# Xilinx_DDR.net
KiCad netlist of a schematic drawn in Altium Designer
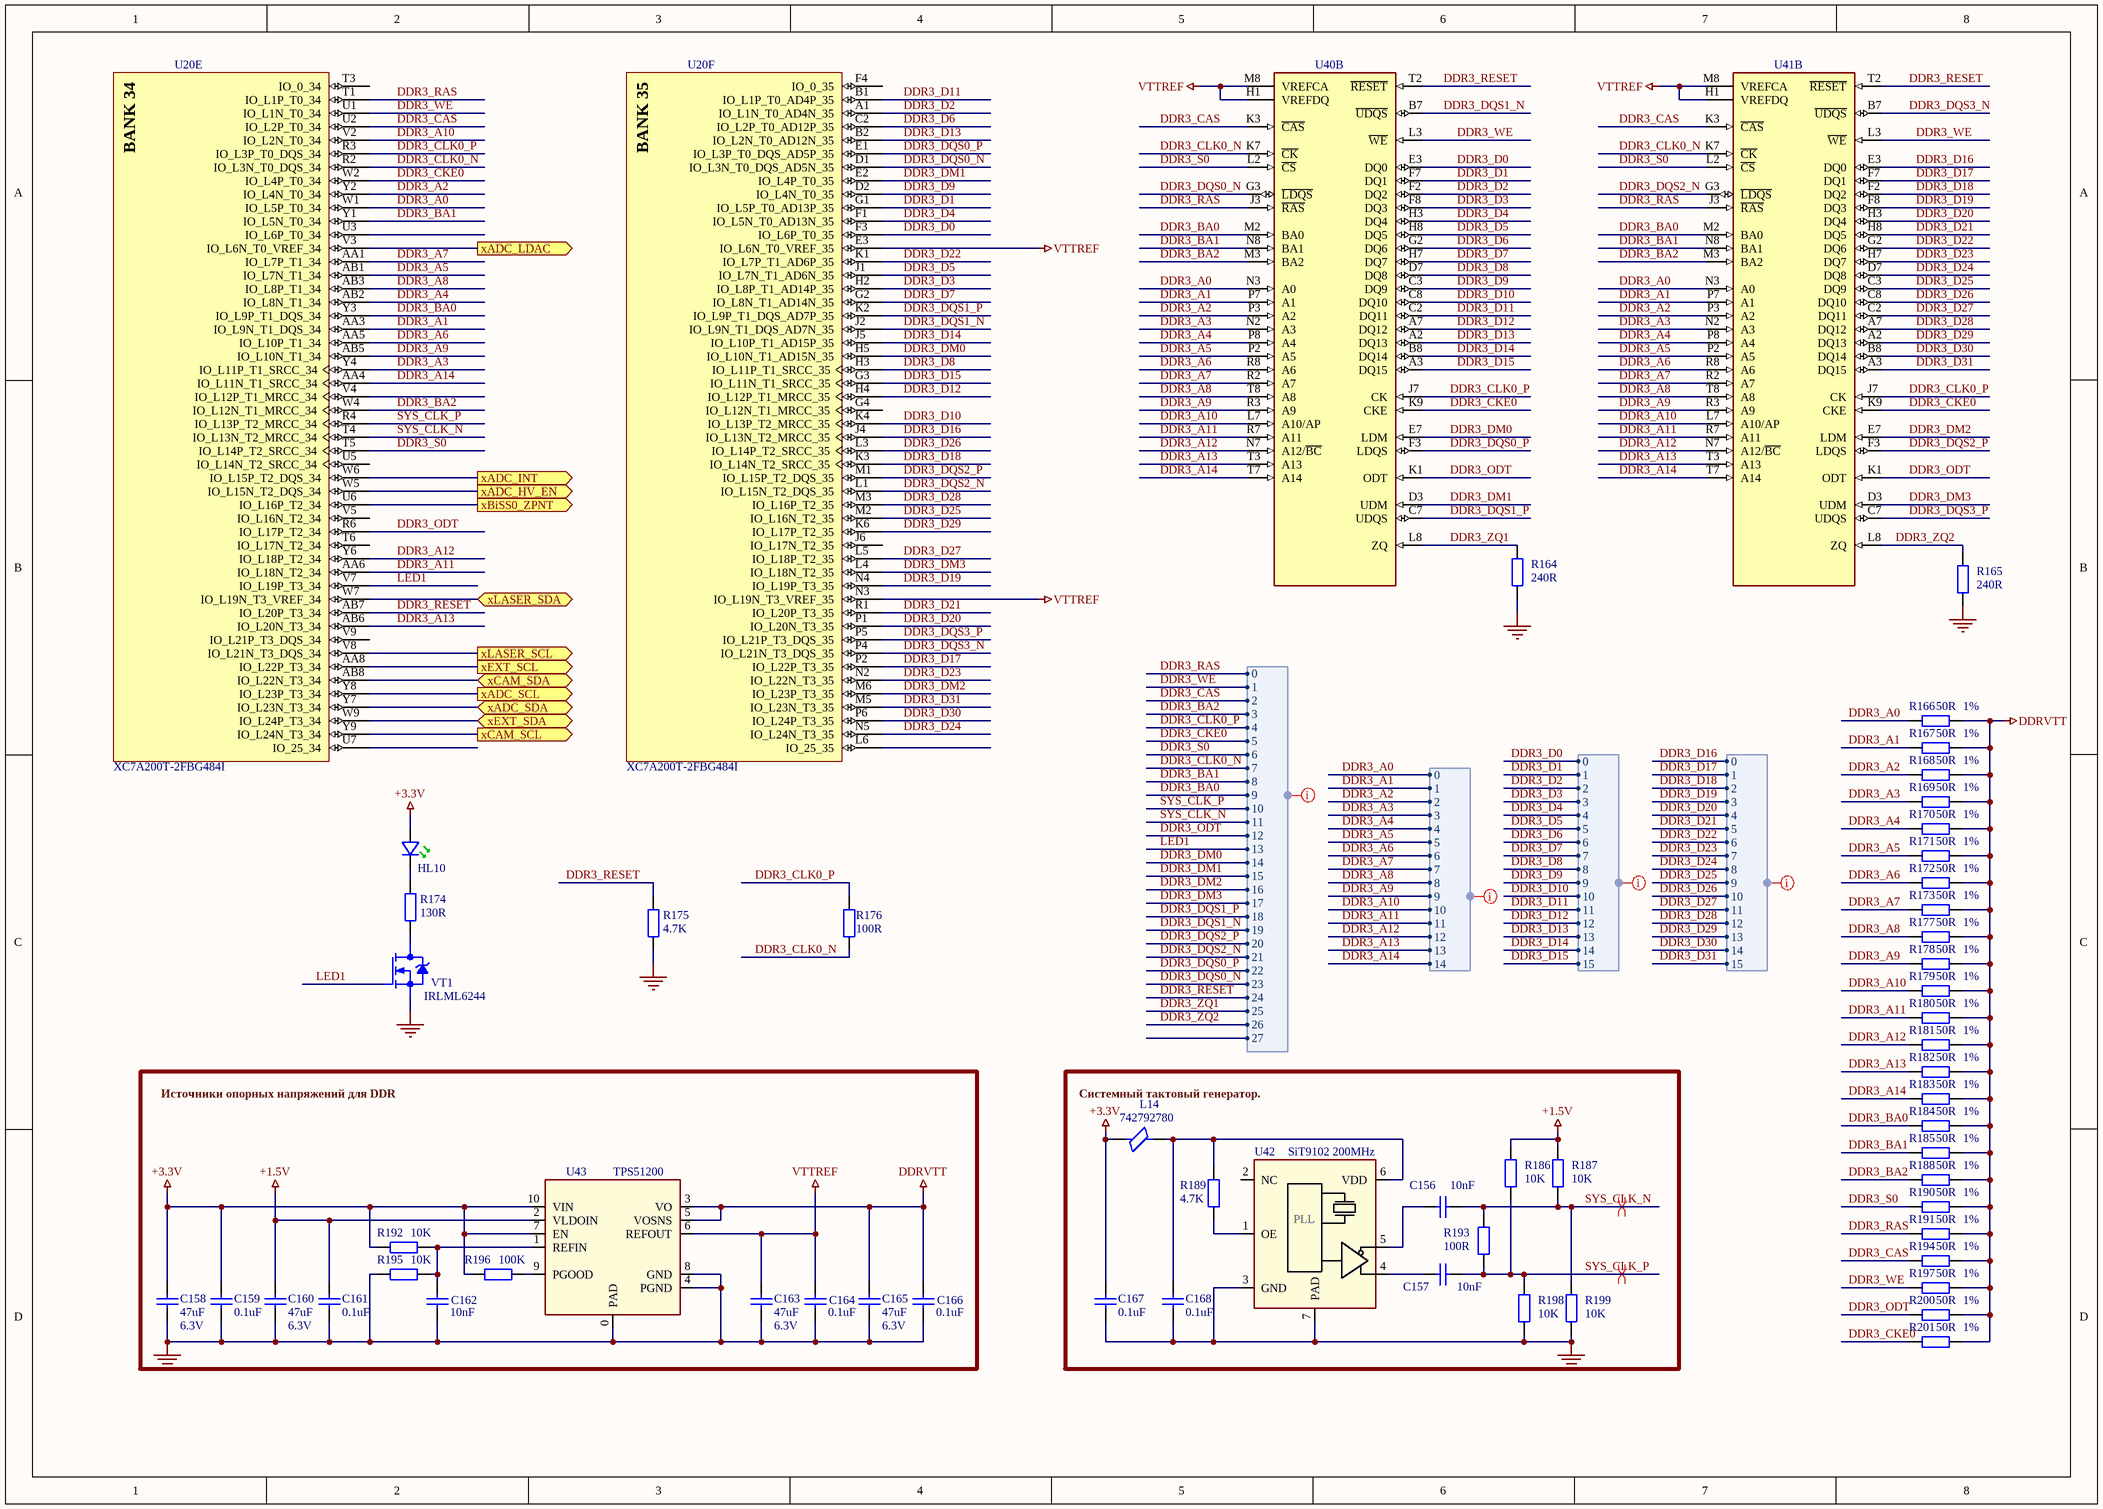
[diagram p0: Xilinx_DDR.SchDoc]

(export (version "E")
  (design (tool "Eeschema 10.0.6"))
  (components
    (comp (ref "C156")
      (value "10nF")
      (footprint "C0402")
      (description "Конденсатор керамический")
      (fields (field (name "VOLTAGE") "25V") (field (name "Comment") "Cap"))
      (libsource (lib "Terra") (part "Cap"))
    )
    (comp (ref "C157")
      (value "10nF")
      (footprint "C0402")
      (description "Конденсатор керамический")
      (fields (field (name "VOLTAGE") "25V") (field (name "Comment") "Cap"))
      (libsource (lib "Terra") (part "Cap"))
    )
    (comp (ref "C158")
      (value "47uF")
      (footprint "C0805")
      (description "C0805C476M9PAC")
      (fields (field (name "VOLTAGE") "6.3V") (field (name "Comment") "Cap"))
      (libsource (lib "Terra") (part "Cap"))
    )
    (comp (ref "C159")
      (value "0.1uF")
      (footprint "C0402")
      (description "Конденсатор керамический")
      (fields (field (name "VOLTAGE") "25V") (field (name "Comment") "Cap"))
      (libsource (lib "Terra") (part "Cap"))
    )
    (comp (ref "C160")
      (value "47uF")
      (footprint "C0805")
      (description "C0805C476M9PAC")
      (fields (field (name "VOLTAGE") "6.3V") (field (name "Comment") "Cap"))
      (libsource (lib "Terra") (part "Cap"))
    )
    (comp (ref "C161")
      (value "0.1uF")
      (footprint "C0402")
      (description "Конденсатор керамический")
      (fields (field (name "VOLTAGE") "25V") (field (name "Comment") "Cap"))
      (libsource (lib "Terra") (part "Cap"))
    )
    (comp (ref "C162")
      (value "10nF")
      (footprint "C0402")
      (description "Конденсатор керамический")
      (fields (field (name "VOLTAGE") "25V") (field (name "Comment") "Cap"))
      (libsource (lib "Terra") (part "Cap"))
    )
    (comp (ref "C163")
      (value "47uF")
      (footprint "C0805")
      (description "C0805C476M9PAC")
      (fields (field (name "VOLTAGE") "6.3V") (field (name "Comment") "Cap"))
      (libsource (lib "Terra") (part "Cap"))
    )
    (comp (ref "C164")
      (value "0.1uF")
      (footprint "C0402")
      (description "Конденсатор керамический")
      (fields (field (name "VOLTAGE") "25V") (field (name "Comment") "Cap"))
      (libsource (lib "Terra") (part "Cap"))
    )
    (comp (ref "C165")
      (value "47uF")
      (footprint "C0805")
      (description "C0805C476M9PAC")
      (fields (field (name "VOLTAGE") "6.3V") (field (name "Comment") "Cap"))
      (libsource (lib "Terra") (part "Cap"))
    )
    (comp (ref "C166")
      (value "0.1uF")
      (footprint "C0402")
      (description "Конденсатор керамический")
      (fields (field (name "VOLTAGE") "25V") (field (name "Comment") "Cap"))
      (libsource (lib "Terra") (part "Cap"))
    )
    (comp (ref "C167")
      (value "0.1uF")
      (footprint "C0402")
      (description "Конденсатор керамический")
      (fields (field (name "VOLTAGE") "25V") (field (name "Comment") "Cap"))
      (libsource (lib "Terra") (part "Cap"))
    )
    (comp (ref "C168")
      (value "0.1uF")
      (footprint "C0402")
      (description "Конденсатор керамический")
      (fields (field (name "VOLTAGE") "25V") (field (name "Comment") "Cap"))
      (libsource (lib "Terra") (part "Cap"))
    )
    (comp (ref "HL10")
      (value "~")
      (footprint "KP-1608_16x08x11_L")
      (description "1.6X0.8mm SMD  LED")
      (libsource (lib "Terra") (part "ledG_KP-1608MGC_KP-1608"))
    )
    (comp (ref "L14")
      (value "742792780")
      (footprint "L0402")
      (description "Wurth Elektronik EMI FILTERS FERRITE BEAD, 220R@100MHz, 0.35R")
      (libsource (lib "Terra") (part "BEAD_FERRITE_SM"))
    )
    (comp (ref "R164")
      (value "240R")
      (footprint "R0402")
      (description "Резистор")
      (fields (field (name "Comment") "Res2"))
      (libsource (lib "") (part "Res2_2"))
    )
    (comp (ref "R165")
      (value "240R")
      (footprint "R0402")
      (description "Резистор")
      (fields (field (name "Comment") "Res2"))
      (libsource (lib "") (part "Res2_2"))
    )
    (comp (ref "R166")
      (value "50R")
      (footprint "R0402")
      (description "Резистор")
      (fields (field (name "PRECISION") "1%") (field (name "Comment") "Res2"))
      (libsource (lib "Terra") (part "Res2"))
    )
    (comp (ref "R167")
      (value "50R")
      (footprint "R0402")
      (description "Резистор")
      (fields (field (name "PRECISION") "1%") (field (name "Comment") "Res2"))
      (libsource (lib "Terra") (part "Res2"))
    )
    (comp (ref "R168")
      (value "50R")
      (footprint "R0402")
      (description "Резистор")
      (fields (field (name "PRECISION") "1%") (field (name "Comment") "Res2"))
      (libsource (lib "Terra") (part "Res2"))
    )
    (comp (ref "R169")
      (value "50R")
      (footprint "R0402")
      (description "Резистор")
      (fields (field (name "PRECISION") "1%") (field (name "Comment") "Res2"))
      (libsource (lib "Terra") (part "Res2"))
    )
    (comp (ref "R170")
      (value "50R")
      (footprint "R0402")
      (description "Резистор")
      (fields (field (name "PRECISION") "1%") (field (name "Comment") "Res2"))
      (libsource (lib "Terra") (part "Res2"))
    )
    (comp (ref "R171")
      (value "50R")
      (footprint "R0402")
      (description "Резистор")
      (fields (field (name "PRECISION") "1%") (field (name "Comment") "Res2"))
      (libsource (lib "Terra") (part "Res2"))
    )
    (comp (ref "R172")
      (value "50R")
      (footprint "R0402")
      (description "Резистор")
      (fields (field (name "PRECISION") "1%") (field (name "Comment") "Res2"))
      (libsource (lib "Terra") (part "Res2"))
    )
    (comp (ref "R173")
      (value "50R")
      (footprint "R0402")
      (description "Резистор")
      (fields (field (name "PRECISION") "1%") (field (name "Comment") "Res2"))
      (libsource (lib "Terra") (part "Res2"))
    )
    (comp (ref "R174")
      (value "130R")
      (footprint "R0402")
      (description "Резистор")
      (fields (field (name "Comment") "Res2"))
      (libsource (lib "") (part "Res2_2"))
    )
    (comp (ref "R175")
      (value "4.7K")
      (footprint "R0402")
      (description "Резистор")
      (fields (field (name "Comment") "Res2"))
      (libsource (lib "") (part "Res2_2"))
    )
    (comp (ref "R176")
      (value "100R")
      (footprint "R0402")
      (description "Резистор")
      (fields (field (name "Comment") "Res2"))
      (libsource (lib "") (part "Res2_1"))
    )
    (comp (ref "R177")
      (value "50R")
      (footprint "R0402")
      (description "Резистор")
      (fields (field (name "PRECISION") "1%") (field (name "Comment") "Res2"))
      (libsource (lib "Terra") (part "Res2"))
    )
    (comp (ref "R178")
      (value "50R")
      (footprint "R0402")
      (description "Резистор")
      (fields (field (name "PRECISION") "1%") (field (name "Comment") "Res2"))
      (libsource (lib "Terra") (part "Res2"))
    )
    (comp (ref "R179")
      (value "50R")
      (footprint "R0402")
      (description "Резистор")
      (fields (field (name "PRECISION") "1%") (field (name "Comment") "Res2"))
      (libsource (lib "Terra") (part "Res2"))
    )
    (comp (ref "R180")
      (value "50R")
      (footprint "R0402")
      (description "Резистор")
      (fields (field (name "PRECISION") "1%") (field (name "Comment") "Res2"))
      (libsource (lib "Terra") (part "Res2"))
    )
    (comp (ref "R181")
      (value "50R")
      (footprint "R0402")
      (description "Резистор")
      (fields (field (name "PRECISION") "1%") (field (name "Comment") "Res2"))
      (libsource (lib "Terra") (part "Res2"))
    )
    (comp (ref "R182")
      (value "50R")
      (footprint "R0402")
      (description "Резистор")
      (fields (field (name "PRECISION") "1%") (field (name "Comment") "Res2"))
      (libsource (lib "Terra") (part "Res2"))
    )
    (comp (ref "R183")
      (value "50R")
      (footprint "R0402")
      (description "Резистор")
      (fields (field (name "PRECISION") "1%") (field (name "Comment") "Res2"))
      (libsource (lib "Terra") (part "Res2"))
    )
    (comp (ref "R184")
      (value "50R")
      (footprint "R0402")
      (description "Резистор")
      (fields (field (name "PRECISION") "1%") (field (name "Comment") "Res2"))
      (libsource (lib "Terra") (part "Res2"))
    )
    (comp (ref "R185")
      (value "50R")
      (footprint "R0402")
      (description "Резистор")
      (fields (field (name "PRECISION") "1%") (field (name "Comment") "Res2"))
      (libsource (lib "Terra") (part "Res2"))
    )
    (comp (ref "R186")
      (value "10K")
      (footprint "R0402")
      (description "Резистор")
      (fields (field (name "Comment") "Res2"))
      (libsource (lib "") (part "Res2_1"))
    )
    (comp (ref "R187")
      (value "10K")
      (footprint "R0402")
      (description "Резистор")
      (fields (field (name "Comment") "Res2"))
      (libsource (lib "") (part "Res2_1"))
    )
    (comp (ref "R188")
      (value "50R")
      (footprint "R0402")
      (description "Резистор")
      (fields (field (name "PRECISION") "1%") (field (name "Comment") "Res2"))
      (libsource (lib "Terra") (part "Res2"))
    )
    (comp (ref "R189")
      (value "4.7K")
      (footprint "R0402")
      (description "Резистор")
      (fields (field (name "Comment") "Res2"))
      (libsource (lib "Terra") (part "Res2"))
    )
    (comp (ref "R190")
      (value "50R")
      (footprint "R0402")
      (description "Резистор")
      (fields (field (name "PRECISION") "1%") (field (name "Comment") "Res2"))
      (libsource (lib "Terra") (part "Res2"))
    )
    (comp (ref "R191")
      (value "50R")
      (footprint "R0402")
      (description "Резистор")
      (fields (field (name "PRECISION") "1%") (field (name "Comment") "Res2"))
      (libsource (lib "Terra") (part "Res2"))
    )
    (comp (ref "R192")
      (value "10K")
      (footprint "R0402")
      (description "Резистор")
      (fields (field (name "Comment") "Res2"))
      (libsource (lib "Terra") (part "Res2"))
    )
    (comp (ref "R193")
      (value "100R")
      (footprint "R0402")
      (description "Резистор")
      (fields (field (name "Comment") "Res2"))
      (libsource (lib "") (part "Res2_1"))
    )
    (comp (ref "R194")
      (value "50R")
      (footprint "R0402")
      (description "Резистор")
      (fields (field (name "PRECISION") "1%") (field (name "Comment") "Res2"))
      (libsource (lib "Terra") (part "Res2"))
    )
    (comp (ref "R195")
      (value "10K")
      (footprint "R0402")
      (description "Резистор")
      (fields (field (name "Comment") "Res2"))
      (libsource (lib "Terra") (part "Res2"))
    )
    (comp (ref "R196")
      (value "100K")
      (footprint "R0402")
      (description "Резистор")
      (fields (field (name "Comment") "Res2"))
      (libsource (lib "Terra") (part "Res2"))
    )
    (comp (ref "R197")
      (value "50R")
      (footprint "R0402")
      (description "Резистор")
      (fields (field (name "PRECISION") "1%") (field (name "Comment") "Res2"))
      (libsource (lib "Terra") (part "Res2"))
    )
    (comp (ref "R198")
      (value "10K")
      (footprint "R0402")
      (description "Резистор")
      (fields (field (name "Comment") "Res2"))
      (libsource (lib "") (part "Res2_1"))
    )
    (comp (ref "R199")
      (value "10K")
      (footprint "R0402")
      (description "Резистор")
      (fields (field (name "Comment") "Res2"))
      (libsource (lib "") (part "Res2_1"))
    )
    (comp (ref "R200")
      (value "50R")
      (footprint "R0402")
      (description "Резистор")
      (fields (field (name "PRECISION") "1%") (field (name "Comment") "Res2"))
      (libsource (lib "Terra") (part "Res2"))
    )
    (comp (ref "R201")
      (value "50R")
      (footprint "R0402")
      (description "Резистор")
      (fields (field (name "PRECISION") "1%") (field (name "Comment") "Res2"))
      (libsource (lib "Terra") (part "Res2"))
    )
    (comp (ref "U20")
      (value "XC7A200T-2FBG484I")
      (footprint "FBG484")
      (description "Artix-7 FPGA, 285 User I/Os, 4 GTP, 484-Ball BGA")
      (fields (field (name "MANUFACTURER") "Xilinx") (field (name "GENERIC PART NUMBER") "XC7A200T"))
      (libsource (lib "Terra") (part "XC7A200T-2FBG484I"))
    )
    (comp (ref "U40")
      (value "MT41J256M16HA-125-E")
      (footprint "FBGA96_9X14_MRN")
      (description "DDR3 SDRAM 32Meg x 16 x 8 banks")
      (libsource (lib "Terra") (part "MT41J256M16HA-125-E"))
    )
    (comp (ref "U41")
      (value "MT41J256M16HA-125-E")
      (footprint "FBGA96_9X14_MRN")
      (description "DDR3 SDRAM 32Meg x 16 x 8 banks")
      (libsource (lib "Terra") (part "MT41J256M16HA-125-E"))
    )
    (comp (ref "U42")
      (value "SiT9102 200MHz")
      (footprint "SMD_AI-243N33E200.00000X_SIT-L")
      (description "200 MHz XO LVDS Oscillator 3.3V")
      (libsource (lib "Terra") (part "SiT9102"))
    )
    (comp (ref "U43")
      (value "TPS51200")
      (footprint "TPS51200AQDRCRQ1")
      (description "Sink and Source DDR Termination Regulator")
      (libsource (lib "Terra") (part "TPS51200"))
    )
    (comp (ref "VT1")
      (value "IRLML6244")
      (footprint "SOT23_123")
      (description "MOSFET-N 1.5V порог переключения.")
      (libsource (lib "*") (part "MOSFET-N/SOT23"))
    )
  )
  (nets
    (net (code "1") (name "+1.5V") (class "Default")
      (node (ref "C160") (pin "1") (pinfunction "1_1") (pintype "passive"))
      (node (ref "C161") (pin "2") (pinfunction "2_2") (pintype "passive"))
      (node (ref "R186") (pin "1") (pinfunction "1_1") (pintype "passive"))
      (node (ref "R187") (pin "1") (pinfunction "1_1") (pintype "passive"))
      (node (ref "U43") (pin "2") (pinfunction "VLDOIN_2") (pintype "passive"))
    )
    (net (code "2") (name "+3.3V") (class "Default")
      (node (ref "C158") (pin "1") (pinfunction "1_1") (pintype "passive"))
      (node (ref "C159") (pin "2") (pinfunction "2_2") (pintype "passive"))
      (node (ref "C167") (pin "2") (pinfunction "2_2") (pintype "passive"))
      (node (ref "HL10") (pin "1") (pinfunction "Anode_1") (pintype "passive"))
      (node (ref "L14") (pin "1") (pinfunction "1_1") (pintype "passive"))
      (node (ref "R192") (pin "1") (pinfunction "1_1") (pintype "passive"))
      (node (ref "R196") (pin "1") (pinfunction "1_1") (pintype "passive"))
      (node (ref "U43") (pin "10") (pinfunction "VIN_10") (pintype "passive"))
      (node (ref "U43") (pin "7") (pinfunction "EN_7") (pintype "passive"))
    )
    (net (code "3") (name "/DDR3_A0") (class "Default")
      (node (ref "R166") (pin "1") (pinfunction "1_1") (pintype "passive"))
      (node (ref "U20") (pin "W1") (pinfunction "IO_L5P_T0_34_W1") (pintype "bidirectional"))
      (node (ref "U40") (pin "N3") (pinfunction "A0_N3") (pintype "input"))
      (node (ref "U41") (pin "N3") (pinfunction "A0_N3") (pintype "input"))
    )
    (net (code "4") (name "/DDR3_A1") (class "Default")
      (node (ref "R167") (pin "1") (pinfunction "1_1") (pintype "passive"))
      (node (ref "U20") (pin "AA3") (pinfunction "IO_L9N_T1_DQS_34_AA3") (pintype "bidirectional"))
      (node (ref "U40") (pin "P7") (pinfunction "A1_P7") (pintype "input"))
      (node (ref "U41") (pin "P7") (pinfunction "A1_P7") (pintype "input"))
    )
    (net (code "5") (name "/DDR3_A2") (class "Default")
      (node (ref "R168") (pin "1") (pinfunction "1_1") (pintype "passive"))
      (node (ref "U20") (pin "Y2") (pinfunction "IO_L4N_T0_34_Y2") (pintype "bidirectional"))
      (node (ref "U40") (pin "P3") (pinfunction "A2_P3") (pintype "input"))
      (node (ref "U41") (pin "P3") (pinfunction "A2_P3") (pintype "input"))
    )
    (net (code "6") (name "/DDR3_A3") (class "Default")
      (node (ref "R169") (pin "1") (pinfunction "1_1") (pintype "passive"))
      (node (ref "U20") (pin "Y4") (pinfunction "IO_L11P_T1_SRCC_34_Y4") (pintype "bidirectional"))
      (node (ref "U40") (pin "N2") (pinfunction "A3_N2") (pintype "input"))
      (node (ref "U41") (pin "N2") (pinfunction "A3_N2") (pintype "input"))
    )
    (net (code "7") (name "/DDR3_A4") (class "Default")
      (node (ref "R170") (pin "1") (pinfunction "1_1") (pintype "passive"))
      (node (ref "U20") (pin "AB2") (pinfunction "IO_L8N_T1_34_AB2") (pintype "bidirectional"))
      (node (ref "U40") (pin "P8") (pinfunction "A4_P8") (pintype "input"))
      (node (ref "U41") (pin "P8") (pinfunction "A4_P8") (pintype "input"))
    )
    (net (code "8") (name "/DDR3_A5") (class "Default")
      (node (ref "R171") (pin "1") (pinfunction "1_1") (pintype "passive"))
      (node (ref "U20") (pin "AB1") (pinfunction "IO_L7N_T1_34_AB1") (pintype "bidirectional"))
      (node (ref "U40") (pin "P2") (pinfunction "A5_P2") (pintype "input"))
      (node (ref "U41") (pin "P2") (pinfunction "A5_P2") (pintype "input"))
    )
    (net (code "9") (name "/DDR3_A6") (class "Default")
      (node (ref "R172") (pin "1") (pinfunction "1_1") (pintype "passive"))
      (node (ref "U20") (pin "AA5") (pinfunction "IO_L10P_T1_34_AA5") (pintype "bidirectional"))
      (node (ref "U40") (pin "R8") (pinfunction "A6_R8") (pintype "input"))
      (node (ref "U41") (pin "R8") (pinfunction "A6_R8") (pintype "input"))
    )
    (net (code "10") (name "/DDR3_A7") (class "Default")
      (node (ref "R173") (pin "1") (pinfunction "1_1") (pintype "passive"))
      (node (ref "U20") (pin "AA1") (pinfunction "IO_L7P_T1_34_AA1") (pintype "bidirectional"))
      (node (ref "U40") (pin "R2") (pinfunction "A7_R2") (pintype "input"))
      (node (ref "U41") (pin "R2") (pinfunction "A7_R2") (pintype "input"))
    )
    (net (code "11") (name "/DDR3_A8") (class "Default")
      (node (ref "R177") (pin "1") (pinfunction "1_1") (pintype "passive"))
      (node (ref "U20") (pin "AB3") (pinfunction "IO_L8P_T1_34_AB3") (pintype "bidirectional"))
      (node (ref "U40") (pin "T8") (pinfunction "A8_T8") (pintype "input"))
      (node (ref "U41") (pin "T8") (pinfunction "A8_T8") (pintype "input"))
    )
    (net (code "12") (name "/DDR3_A9") (class "Default")
      (node (ref "R178") (pin "1") (pinfunction "1_1") (pintype "passive"))
      (node (ref "U20") (pin "AB5") (pinfunction "IO_L10N_T1_34_AB5") (pintype "bidirectional"))
      (node (ref "U40") (pin "R3") (pinfunction "A9_R3") (pintype "input"))
      (node (ref "U41") (pin "R3") (pinfunction "A9_R3") (pintype "input"))
    )
    (net (code "13") (name "/DDR3_A10") (class "Default")
      (node (ref "R179") (pin "1") (pinfunction "1_1") (pintype "passive"))
      (node (ref "U20") (pin "V2") (pinfunction "IO_L2N_T0_34_V2") (pintype "bidirectional"))
      (node (ref "U40") (pin "L7") (pinfunction "A10/AP_L7") (pintype "input"))
      (node (ref "U41") (pin "L7") (pinfunction "A10/AP_L7") (pintype "input"))
    )
    (net (code "14") (name "/DDR3_A11") (class "Default")
      (node (ref "R180") (pin "1") (pinfunction "1_1") (pintype "passive"))
      (node (ref "U20") (pin "AA6") (pinfunction "IO_L18N_T2_34_AA6") (pintype "bidirectional"))
      (node (ref "U40") (pin "R7") (pinfunction "A11_R7") (pintype "input"))
      (node (ref "U41") (pin "R7") (pinfunction "A11_R7") (pintype "input"))
    )
    (net (code "15") (name "/DDR3_A12") (class "Default")
      (node (ref "R181") (pin "1") (pinfunction "1_1") (pintype "passive"))
      (node (ref "U20") (pin "Y6") (pinfunction "IO_L18P_T2_34_Y6") (pintype "bidirectional"))
      (node (ref "U40") (pin "N7") (pinfunction "A12/~{BC}_N7") (pintype "input"))
      (node (ref "U41") (pin "N7") (pinfunction "A12/~{BC}_N7") (pintype "input"))
    )
    (net (code "16") (name "/DDR3_A13") (class "Default")
      (node (ref "R182") (pin "1") (pinfunction "1_1") (pintype "passive"))
      (node (ref "U20") (pin "AB6") (pinfunction "IO_L20N_T3_34_AB6") (pintype "bidirectional"))
      (node (ref "U40") (pin "T3") (pinfunction "A13_T3") (pintype "input"))
      (node (ref "U41") (pin "T3") (pinfunction "A13_T3") (pintype "input"))
    )
    (net (code "17") (name "/DDR3_A14") (class "Default")
      (node (ref "R183") (pin "1") (pinfunction "1_1") (pintype "passive"))
      (node (ref "U20") (pin "AA4") (pinfunction "IO_L11N_T1_SRCC_34_AA4") (pintype "bidirectional"))
      (node (ref "U40") (pin "T7") (pinfunction "A14_T7") (pintype "input"))
      (node (ref "U41") (pin "T7") (pinfunction "A14_T7") (pintype "input"))
    )
    (net (code "18") (name "/DDR3_BA0") (class "Default")
      (node (ref "R184") (pin "1") (pinfunction "1_1") (pintype "passive"))
      (node (ref "U20") (pin "Y3") (pinfunction "IO_L9P_T1_DQS_34_Y3") (pintype "bidirectional"))
      (node (ref "U40") (pin "M2") (pinfunction "BA0_M2") (pintype "input"))
      (node (ref "U41") (pin "M2") (pinfunction "BA0_M2") (pintype "input"))
    )
    (net (code "19") (name "/DDR3_BA1") (class "Default")
      (node (ref "R185") (pin "1") (pinfunction "1_1") (pintype "passive"))
      (node (ref "U20") (pin "Y1") (pinfunction "IO_L5N_T0_34_Y1") (pintype "bidirectional"))
      (node (ref "U40") (pin "N8") (pinfunction "BA1_N8") (pintype "input"))
      (node (ref "U41") (pin "N8") (pinfunction "BA1_N8") (pintype "input"))
    )
    (net (code "20") (name "/DDR3_BA2") (class "Default")
      (node (ref "R188") (pin "1") (pinfunction "1_1") (pintype "passive"))
      (node (ref "U20") (pin "W4") (pinfunction "IO_L12N_T1_MRCC_34_W4") (pintype "bidirectional"))
      (node (ref "U40") (pin "M3") (pinfunction "BA2_M3") (pintype "input"))
      (node (ref "U41") (pin "M3") (pinfunction "BA2_M3") (pintype "input"))
    )
    (net (code "21") (name "/DDR3_CAS") (class "Default")
      (node (ref "R194") (pin "1") (pinfunction "1_1") (pintype "passive"))
      (node (ref "U20") (pin "U2") (pinfunction "IO_L2P_T0_34_U2") (pintype "bidirectional"))
      (node (ref "U40") (pin "K3") (pinfunction "~{CAS}_K3") (pintype "input"))
      (node (ref "U41") (pin "K3") (pinfunction "~{CAS}_K3") (pintype "input"))
    )
    (net (code "22") (name "/DDR3_CKE0") (class "Default")
      (node (ref "R201") (pin "1") (pinfunction "1_1") (pintype "passive"))
      (node (ref "U20") (pin "W2") (pinfunction "IO_L4P_T0_34_W2") (pintype "bidirectional"))
      (node (ref "U40") (pin "K9") (pinfunction "CKE_K9") (pintype "input"))
      (node (ref "U41") (pin "K9") (pinfunction "CKE_K9") (pintype "input"))
    )
    (net (code "23") (name "/DDR3_CLK0_N") (class "Default")
      (node (ref "R176") (pin "2") (pinfunction "2_2") (pintype "passive"))
      (node (ref "U20") (pin "R2") (pinfunction "IO_L3N_T0_DQS_34_R2") (pintype "bidirectional"))
      (node (ref "U40") (pin "K7") (pinfunction "~{CK}_K7") (pintype "input"))
      (node (ref "U41") (pin "K7") (pinfunction "~{CK}_K7") (pintype "input"))
    )
    (net (code "24") (name "/DDR3_CLK0_P") (class "Default")
      (node (ref "R176") (pin "1") (pinfunction "1_1") (pintype "passive"))
      (node (ref "U20") (pin "R3") (pinfunction "IO_L3P_T0_DQS_34_R3") (pintype "bidirectional"))
      (node (ref "U40") (pin "J7") (pinfunction "CK_J7") (pintype "input"))
      (node (ref "U41") (pin "J7") (pinfunction "CK_J7") (pintype "input"))
    )
    (net (code "25") (name "/DDR3_D0") (class "Default")
      (node (ref "U20") (pin "F3") (pinfunction "IO_L6P_T0_35_F3") (pintype "bidirectional"))
      (node (ref "U40") (pin "E3") (pinfunction "DQ0_E3") (pintype "bidirectional"))
    )
    (net (code "26") (name "/DDR3_D1") (class "Default")
      (node (ref "U20") (pin "G1") (pinfunction "IO_L5P_T0_AD13P_35_G1") (pintype "bidirectional"))
      (node (ref "U40") (pin "F7") (pinfunction "DQ1_F7") (pintype "bidirectional"))
    )
    (net (code "27") (name "/DDR3_D2") (class "Default")
      (node (ref "U20") (pin "A1") (pinfunction "IO_L1N_T0_AD4N_35_A1") (pintype "bidirectional"))
      (node (ref "U40") (pin "F2") (pinfunction "DQ2_F2") (pintype "bidirectional"))
    )
    (net (code "28") (name "/DDR3_D3") (class "Default")
      (node (ref "U20") (pin "H2") (pinfunction "IO_L8P_T1_AD14P_35_H2") (pintype "bidirectional"))
      (node (ref "U40") (pin "F8") (pinfunction "DQ3_F8") (pintype "bidirectional"))
    )
    (net (code "29") (name "/DDR3_D4") (class "Default")
      (node (ref "U20") (pin "F1") (pinfunction "IO_L5N_T0_AD13N_35_F1") (pintype "bidirectional"))
      (node (ref "U40") (pin "H3") (pinfunction "DQ4_H3") (pintype "bidirectional"))
    )
    (net (code "30") (name "/DDR3_D5") (class "Default")
      (node (ref "U20") (pin "J1") (pinfunction "IO_L7N_T1_AD6N_35_J1") (pintype "bidirectional"))
      (node (ref "U40") (pin "H8") (pinfunction "DQ5_H8") (pintype "bidirectional"))
    )
    (net (code "31") (name "/DDR3_D6") (class "Default")
      (node (ref "U20") (pin "C2") (pinfunction "IO_L2P_T0_AD12P_35_C2") (pintype "bidirectional"))
      (node (ref "U40") (pin "G2") (pinfunction "DQ6_G2") (pintype "bidirectional"))
    )
    (net (code "32") (name "/DDR3_D7") (class "Default")
      (node (ref "U20") (pin "G2") (pinfunction "IO_L8N_T1_AD14N_35_G2") (pintype "bidirectional"))
      (node (ref "U40") (pin "H7") (pinfunction "DQ7_H7") (pintype "bidirectional"))
    )
    (net (code "33") (name "/DDR3_D8") (class "Default")
      (node (ref "U20") (pin "H3") (pinfunction "IO_L11P_T1_SRCC_35_H3") (pintype "bidirectional"))
      (node (ref "U40") (pin "D7") (pinfunction "DQ8_D7") (pintype "bidirectional"))
    )
    (net (code "34") (name "/DDR3_D9") (class "Default")
      (node (ref "U20") (pin "D2") (pinfunction "IO_L4N_T0_35_D2") (pintype "bidirectional"))
      (node (ref "U40") (pin "C3") (pinfunction "DQ9_C3") (pintype "bidirectional"))
    )
    (net (code "35") (name "/DDR3_D10") (class "Default")
      (node (ref "U20") (pin "K4") (pinfunction "IO_L13P_T2_MRCC_35_K4") (pintype "bidirectional"))
      (node (ref "U40") (pin "C8") (pinfunction "DQ10_C8") (pintype "bidirectional"))
    )
    (net (code "36") (name "/DDR3_D11") (class "Default")
      (node (ref "U20") (pin "B1") (pinfunction "IO_L1P_T0_AD4P_35_B1") (pintype "bidirectional"))
      (node (ref "U40") (pin "C2") (pinfunction "DQ11_C2") (pintype "bidirectional"))
    )
    (net (code "37") (name "/DDR3_D12") (class "Default")
      (node (ref "U20") (pin "H4") (pinfunction "IO_L12P_T1_MRCC_35_H4") (pintype "bidirectional"))
      (node (ref "U40") (pin "A7") (pinfunction "DQ12_A7") (pintype "bidirectional"))
    )
    (net (code "38") (name "/DDR3_D13") (class "Default")
      (node (ref "U20") (pin "B2") (pinfunction "IO_L2N_T0_AD12N_35_B2") (pintype "bidirectional"))
      (node (ref "U40") (pin "A2") (pinfunction "DQ13_A2") (pintype "bidirectional"))
    )
    (net (code "39") (name "/DDR3_D14") (class "Default")
      (node (ref "U20") (pin "J5") (pinfunction "IO_L10P_T1_AD15P_35_J5") (pintype "bidirectional"))
      (node (ref "U40") (pin "B8") (pinfunction "DQ14_B8") (pintype "bidirectional"))
    )
    (net (code "40") (name "/DDR3_D15") (class "Default")
      (node (ref "U20") (pin "G3") (pinfunction "IO_L11N_T1_SRCC_35_G3") (pintype "bidirectional"))
      (node (ref "U40") (pin "A3") (pinfunction "DQ15_A3") (pintype "bidirectional"))
    )
    (net (code "41") (name "/DDR3_D16") (class "Default")
      (node (ref "U20") (pin "J4") (pinfunction "IO_L13N_T2_MRCC_35_J4") (pintype "bidirectional"))
      (node (ref "U41") (pin "E3") (pinfunction "DQ0_E3") (pintype "bidirectional"))
    )
    (net (code "42") (name "/DDR3_D17") (class "Default")
      (node (ref "U20") (pin "P2") (pinfunction "IO_L22P_T3_35_P2") (pintype "bidirectional"))
      (node (ref "U41") (pin "F7") (pinfunction "DQ1_F7") (pintype "bidirectional"))
    )
    (net (code "43") (name "/DDR3_D18") (class "Default")
      (node (ref "U20") (pin "K3") (pinfunction "IO_L14N_T2_SRCC_35_K3") (pintype "bidirectional"))
      (node (ref "U41") (pin "F2") (pinfunction "DQ2_F2") (pintype "bidirectional"))
    )
    (net (code "44") (name "/DDR3_D19") (class "Default")
      (node (ref "U20") (pin "N4") (pinfunction "IO_L19P_T3_35_N4") (pintype "bidirectional"))
      (node (ref "U41") (pin "F8") (pinfunction "DQ3_F8") (pintype "bidirectional"))
    )
    (net (code "45") (name "/DDR3_D20") (class "Default")
      (node (ref "U20") (pin "P1") (pinfunction "IO_L20N_T3_35_P1") (pintype "bidirectional"))
      (node (ref "U41") (pin "H3") (pinfunction "DQ4_H3") (pintype "bidirectional"))
    )
    (net (code "46") (name "/DDR3_D21") (class "Default")
      (node (ref "U20") (pin "R1") (pinfunction "IO_L20P_T3_35_R1") (pintype "bidirectional"))
      (node (ref "U41") (pin "H8") (pinfunction "DQ5_H8") (pintype "bidirectional"))
    )
    (net (code "47") (name "/DDR3_D22") (class "Default")
      (node (ref "U20") (pin "K1") (pinfunction "IO_L7P_T1_AD6P_35_K1") (pintype "bidirectional"))
      (node (ref "U41") (pin "G2") (pinfunction "DQ6_G2") (pintype "bidirectional"))
    )
    (net (code "48") (name "/DDR3_D23") (class "Default")
      (node (ref "U20") (pin "N2") (pinfunction "IO_L22N_T3_35_N2") (pintype "bidirectional"))
      (node (ref "U41") (pin "H7") (pinfunction "DQ7_H7") (pintype "bidirectional"))
    )
    (net (code "49") (name "/DDR3_D24") (class "Default")
      (node (ref "U20") (pin "N5") (pinfunction "IO_L24N_T3_35_N5") (pintype "bidirectional"))
      (node (ref "U41") (pin "D7") (pinfunction "DQ8_D7") (pintype "bidirectional"))
    )
    (net (code "50") (name "/DDR3_D25") (class "Default")
      (node (ref "U20") (pin "M2") (pinfunction "IO_L16N_T2_35_M2") (pintype "bidirectional"))
      (node (ref "U41") (pin "C3") (pinfunction "DQ9_C3") (pintype "bidirectional"))
    )
    (net (code "51") (name "/DDR3_D26") (class "Default")
      (node (ref "U20") (pin "L3") (pinfunction "IO_L14P_T2_SRCC_35_L3") (pintype "bidirectional"))
      (node (ref "U41") (pin "C8") (pinfunction "DQ10_C8") (pintype "bidirectional"))
    )
    (net (code "52") (name "/DDR3_D27") (class "Default")
      (node (ref "U20") (pin "L5") (pinfunction "IO_L18P_T2_35_L5") (pintype "bidirectional"))
      (node (ref "U41") (pin "C2") (pinfunction "DQ11_C2") (pintype "bidirectional"))
    )
    (net (code "53") (name "/DDR3_D28") (class "Default")
      (node (ref "U20") (pin "M3") (pinfunction "IO_L16P_T2_35_M3") (pintype "bidirectional"))
      (node (ref "U41") (pin "A7") (pinfunction "DQ12_A7") (pintype "bidirectional"))
    )
    (net (code "54") (name "/DDR3_D29") (class "Default")
      (node (ref "U20") (pin "K6") (pinfunction "IO_L17P_T2_35_K6") (pintype "bidirectional"))
      (node (ref "U41") (pin "A2") (pinfunction "DQ13_A2") (pintype "bidirectional"))
    )
    (net (code "55") (name "/DDR3_D30") (class "Default")
      (node (ref "U20") (pin "P6") (pinfunction "IO_L24P_T3_35_P6") (pintype "bidirectional"))
      (node (ref "U41") (pin "B8") (pinfunction "DQ14_B8") (pintype "bidirectional"))
    )
    (net (code "56") (name "/DDR3_D31") (class "Default")
      (node (ref "U20") (pin "M5") (pinfunction "IO_L23N_T3_35_M5") (pintype "bidirectional"))
      (node (ref "U41") (pin "A3") (pinfunction "DQ15_A3") (pintype "bidirectional"))
    )
    (net (code "57") (name "/DDR3_DM0") (class "Default")
      (node (ref "U20") (pin "H5") (pinfunction "IO_L10N_T1_AD15N_35_H5") (pintype "bidirectional"))
      (node (ref "U40") (pin "E7") (pinfunction "LDM_E7") (pintype "input"))
    )
    (net (code "58") (name "/DDR3_DM1") (class "Default")
      (node (ref "U20") (pin "E2") (pinfunction "IO_L4P_T0_35_E2") (pintype "bidirectional"))
      (node (ref "U40") (pin "D3") (pinfunction "UDM_D3") (pintype "input"))
    )
    (net (code "59") (name "/DDR3_DM2") (class "Default")
      (node (ref "U20") (pin "M6") (pinfunction "IO_L23P_T3_35_M6") (pintype "bidirectional"))
      (node (ref "U41") (pin "E7") (pinfunction "LDM_E7") (pintype "input"))
    )
    (net (code "60") (name "/DDR3_DM3") (class "Default")
      (node (ref "U20") (pin "L4") (pinfunction "IO_L18N_T2_35_L4") (pintype "bidirectional"))
      (node (ref "U41") (pin "D3") (pinfunction "UDM_D3") (pintype "input"))
    )
    (net (code "61") (name "/DDR3_DQS0_N") (class "Default")
      (node (ref "U20") (pin "D1") (pinfunction "IO_L3N_T0_DQS_AD5N_35_D1") (pintype "bidirectional"))
      (node (ref "U40") (pin "G3") (pinfunction "~{LDQS}_G3") (pintype "bidirectional"))
    )
    (net (code "62") (name "/DDR3_DQS0_P") (class "Default")
      (node (ref "U20") (pin "E1") (pinfunction "IO_L3P_T0_DQS_AD5P_35_E1") (pintype "bidirectional"))
      (node (ref "U40") (pin "F3") (pinfunction "LDQS_F3") (pintype "bidirectional"))
    )
    (net (code "63") (name "/DDR3_DQS1_N") (class "Default")
      (node (ref "U20") (pin "J2") (pinfunction "IO_L9N_T1_DQS_AD7N_35_J2") (pintype "bidirectional"))
      (node (ref "U40") (pin "B7") (pinfunction "~{UDQS}_B7") (pintype "bidirectional"))
    )
    (net (code "64") (name "/DDR3_DQS1_P") (class "Default")
      (node (ref "U20") (pin "K2") (pinfunction "IO_L9P_T1_DQS_AD7P_35_K2") (pintype "bidirectional"))
      (node (ref "U40") (pin "C7") (pinfunction "UDQS_C7") (pintype "bidirectional"))
    )
    (net (code "65") (name "/DDR3_DQS2_N") (class "Default")
      (node (ref "U20") (pin "L1") (pinfunction "IO_L15N_T2_DQS_35_L1") (pintype "bidirectional"))
      (node (ref "U41") (pin "G3") (pinfunction "~{LDQS}_G3") (pintype "bidirectional"))
    )
    (net (code "66") (name "/DDR3_DQS2_P") (class "Default")
      (node (ref "U20") (pin "M1") (pinfunction "IO_L15P_T2_DQS_35_M1") (pintype "bidirectional"))
      (node (ref "U41") (pin "F3") (pinfunction "LDQS_F3") (pintype "bidirectional"))
    )
    (net (code "67") (name "/DDR3_DQS3_N") (class "Default")
      (node (ref "U20") (pin "P4") (pinfunction "IO_L21N_T3_DQS_35_P4") (pintype "bidirectional"))
      (node (ref "U41") (pin "B7") (pinfunction "~{UDQS}_B7") (pintype "bidirectional"))
    )
    (net (code "68") (name "/DDR3_DQS3_P") (class "Default")
      (node (ref "U20") (pin "P5") (pinfunction "IO_L21P_T3_DQS_35_P5") (pintype "bidirectional"))
      (node (ref "U41") (pin "C7") (pinfunction "UDQS_C7") (pintype "bidirectional"))
    )
    (net (code "69") (name "/DDR3_ODT") (class "Default")
      (node (ref "R200") (pin "1") (pinfunction "1_1") (pintype "passive"))
      (node (ref "U20") (pin "R6") (pinfunction "IO_L17P_T2_34_R6") (pintype "bidirectional"))
      (node (ref "U40") (pin "K1") (pinfunction "ODT_K1") (pintype "input"))
      (node (ref "U41") (pin "K1") (pinfunction "ODT_K1") (pintype "input"))
    )
    (net (code "70") (name "/DDR3_RAS") (class "Default")
      (node (ref "R191") (pin "1") (pinfunction "1_1") (pintype "passive"))
      (node (ref "U20") (pin "T1") (pinfunction "IO_L1P_T0_34_T1") (pintype "bidirectional"))
      (node (ref "U40") (pin "J3") (pinfunction "~{RAS}_J3") (pintype "input"))
      (node (ref "U41") (pin "J3") (pinfunction "~{RAS}_J3") (pintype "input"))
    )
    (net (code "71") (name "/DDR3_RESET") (class "Default")
      (node (ref "R175") (pin "2") (pinfunction "2_2") (pintype "passive"))
      (node (ref "U20") (pin "AB7") (pinfunction "IO_L20P_T3_34_AB7") (pintype "bidirectional"))
      (node (ref "U40") (pin "T2") (pinfunction "~{RESET}_T2") (pintype "input"))
      (node (ref "U41") (pin "T2") (pinfunction "~{RESET}_T2") (pintype "input"))
    )
    (net (code "72") (name "/DDR3_S0") (class "Default")
      (node (ref "R190") (pin "1") (pinfunction "1_1") (pintype "passive"))
      (node (ref "U20") (pin "T5") (pinfunction "IO_L14P_T2_SRCC_34_T5") (pintype "bidirectional"))
      (node (ref "U40") (pin "L2") (pinfunction "~{CS}_L2") (pintype "input"))
      (node (ref "U41") (pin "L2") (pinfunction "~{CS}_L2") (pintype "input"))
    )
    (net (code "73") (name "/DDR3_WE") (class "Default")
      (node (ref "R197") (pin "1") (pinfunction "1_1") (pintype "passive"))
      (node (ref "U20") (pin "U1") (pinfunction "IO_L1N_T0_34_U1") (pintype "bidirectional"))
      (node (ref "U40") (pin "L3") (pinfunction "~{WE}_L3") (pintype "input"))
      (node (ref "U41") (pin "L3") (pinfunction "~{WE}_L3") (pintype "input"))
    )
    (net (code "74") (name "/DDR3_ZQ1") (class "Default")
      (node (ref "R164") (pin "2") (pinfunction "2_2") (pintype "passive"))
      (node (ref "U40") (pin "L8") (pinfunction "ZQ_L8") (pintype "input"))
    )
    (net (code "75") (name "/DDR3_ZQ2") (class "Default")
      (node (ref "R165") (pin "2") (pinfunction "2_2") (pintype "passive"))
      (node (ref "U41") (pin "L8") (pinfunction "ZQ_L8") (pintype "input"))
    )
    (net (code "76") (name "/LED1") (class "Default")
      (node (ref "U20") (pin "V7") (pinfunction "IO_L19P_T3_34_V7") (pintype "bidirectional"))
      (node (ref "VT1") (pin "1") (pinfunction "Gate_1") (pintype "passive"))
    )
    (net (code "77") (name "/SYS_CLK_N") (class "Default")
      (node (ref "C156") (pin "2") (pinfunction "2_2") (pintype "passive"))
      (node (ref "R187") (pin "2") (pinfunction "2_2") (pintype "passive"))
      (node (ref "R193") (pin "1") (pinfunction "1_1") (pintype "passive"))
      (node (ref "R199") (pin "1") (pinfunction "1_1") (pintype "passive"))
      (node (ref "U20") (pin "T4") (pinfunction "IO_L13N_T2_MRCC_34_T4") (pintype "bidirectional"))
    )
    (net (code "78") (name "/SYS_CLK_P") (class "Default")
      (node (ref "C157") (pin "2") (pinfunction "2_2") (pintype "passive"))
      (node (ref "R186") (pin "2") (pinfunction "2_2") (pintype "passive"))
      (node (ref "R193") (pin "2") (pinfunction "2_2") (pintype "passive"))
      (node (ref "R198") (pin "1") (pinfunction "1_1") (pintype "passive"))
      (node (ref "U20") (pin "R4") (pinfunction "IO_L13P_T2_MRCC_34_R4") (pintype "bidirectional"))
    )
    (net (code "79") (name "/xADC_HV_EN") (class "Default")
      (node (ref "U20") (pin "W5") (pinfunction "IO_L15N_T2_DQS_34_W5") (pintype "bidirectional"))
    )
    (net (code "80") (name "/xADC_INT") (class "Default")
      (node (ref "U20") (pin "W6") (pinfunction "IO_L15P_T2_DQS_34_W6") (pintype "bidirectional"))
    )
    (net (code "81") (name "/xADC_LDAC") (class "Default")
      (node (ref "U20") (pin "V3") (pinfunction "IO_L6N_T0_VREF_34_V3") (pintype "bidirectional"))
    )
    (net (code "82") (name "/xADC_SCL") (class "Default")
      (node (ref "U20") (pin "Y8") (pinfunction "IO_L23P_T3_34_Y8") (pintype "bidirectional"))
    )
    (net (code "83") (name "/xADC_SDA") (class "Default")
      (node (ref "U20") (pin "Y7") (pinfunction "IO_L23N_T3_34_Y7") (pintype "bidirectional"))
    )
    (net (code "84") (name "/xBiSS0_ZPNT") (class "Default")
      (node (ref "U20") (pin "U6") (pinfunction "IO_L16P_T2_34_U6") (pintype "bidirectional"))
    )
    (net (code "85") (name "/xCAM_SCL") (class "Default")
      (node (ref "U20") (pin "Y9") (pinfunction "IO_L24N_T3_34_Y9") (pintype "bidirectional"))
    )
    (net (code "86") (name "/xCAM_SDA") (class "Default")
      (node (ref "U20") (pin "AB8") (pinfunction "IO_L22N_T3_34_AB8") (pintype "bidirectional"))
    )
    (net (code "87") (name "/xEXT_SCL") (class "Default")
      (node (ref "U20") (pin "AA8") (pinfunction "IO_L22P_T3_34_AA8") (pintype "bidirectional"))
    )
    (net (code "88") (name "/xEXT_SDA") (class "Default")
      (node (ref "U20") (pin "W9") (pinfunction "IO_L24P_T3_34_W9") (pintype "bidirectional"))
    )
    (net (code "89") (name "/xLASER_SCL") (class "Default")
      (node (ref "U20") (pin "V8") (pinfunction "IO_L21N_T3_DQS_34_V8") (pintype "bidirectional"))
    )
    (net (code "90") (name "/xLASER_SDA") (class "Default")
      (node (ref "U20") (pin "W7") (pinfunction "IO_L19N_T3_VREF_34_W7") (pintype "bidirectional"))
    )
    (net (code "91") (name "DDRVTT") (class "Default")
      (node (ref "C165") (pin "1") (pinfunction "1_1") (pintype "passive"))
      (node (ref "C166") (pin "1") (pinfunction "1_1") (pintype "passive"))
      (node (ref "R166") (pin "2") (pinfunction "2_2") (pintype "passive"))
      (node (ref "R167") (pin "2") (pinfunction "2_2") (pintype "passive"))
      (node (ref "R168") (pin "2") (pinfunction "2_2") (pintype "passive"))
      (node (ref "R169") (pin "2") (pinfunction "2_2") (pintype "passive"))
      (node (ref "R170") (pin "2") (pinfunction "2_2") (pintype "passive"))
      (node (ref "R171") (pin "2") (pinfunction "2_2") (pintype "passive"))
      (node (ref "R172") (pin "2") (pinfunction "2_2") (pintype "passive"))
      (node (ref "R173") (pin "2") (pinfunction "2_2") (pintype "passive"))
      (node (ref "R177") (pin "2") (pinfunction "2_2") (pintype "passive"))
      (node (ref "R178") (pin "2") (pinfunction "2_2") (pintype "passive"))
      (node (ref "R179") (pin "2") (pinfunction "2_2") (pintype "passive"))
      (node (ref "R180") (pin "2") (pinfunction "2_2") (pintype "passive"))
      (node (ref "R181") (pin "2") (pinfunction "2_2") (pintype "passive"))
      (node (ref "R182") (pin "2") (pinfunction "2_2") (pintype "passive"))
      (node (ref "R183") (pin "2") (pinfunction "2_2") (pintype "passive"))
      (node (ref "R184") (pin "2") (pinfunction "2_2") (pintype "passive"))
      (node (ref "R185") (pin "2") (pinfunction "2_2") (pintype "passive"))
      (node (ref "R188") (pin "2") (pinfunction "2_2") (pintype "passive"))
      (node (ref "R190") (pin "2") (pinfunction "2_2") (pintype "passive"))
      (node (ref "R191") (pin "2") (pinfunction "2_2") (pintype "passive"))
      (node (ref "R194") (pin "2") (pinfunction "2_2") (pintype "passive"))
      (node (ref "R197") (pin "2") (pinfunction "2_2") (pintype "passive"))
      (node (ref "R200") (pin "2") (pinfunction "2_2") (pintype "passive"))
      (node (ref "R201") (pin "2") (pinfunction "2_2") (pintype "passive"))
      (node (ref "U43") (pin "3") (pinfunction "VO_3") (pintype "passive"))
      (node (ref "U43") (pin "5") (pinfunction "VOSNS_5") (pintype "passive"))
    )
    (net (code "92") (name "GND") (class "Default")
      (node (ref "C158") (pin "2") (pinfunction "2_2") (pintype "passive"))
      (node (ref "C159") (pin "1") (pinfunction "1_1") (pintype "passive"))
      (node (ref "C160") (pin "2") (pinfunction "2_2") (pintype "passive"))
      (node (ref "C161") (pin "1") (pinfunction "1_1") (pintype "passive"))
      (node (ref "C162") (pin "2") (pinfunction "2_2") (pintype "passive"))
      (node (ref "C163") (pin "2") (pinfunction "2_2") (pintype "passive"))
      (node (ref "C164") (pin "2") (pinfunction "2_2") (pintype "passive"))
      (node (ref "C165") (pin "2") (pinfunction "2_2") (pintype "passive"))
      (node (ref "C166") (pin "2") (pinfunction "2_2") (pintype "passive"))
      (node (ref "C167") (pin "1") (pinfunction "1_1") (pintype "passive"))
      (node (ref "C168") (pin "1") (pinfunction "1_1") (pintype "passive"))
      (node (ref "R164") (pin "1") (pinfunction "1_1") (pintype "passive"))
      (node (ref "R165") (pin "1") (pinfunction "1_1") (pintype "passive"))
      (node (ref "R175") (pin "1") (pinfunction "1_1") (pintype "passive"))
      (node (ref "R195") (pin "1") (pinfunction "1_1") (pintype "passive"))
      (node (ref "R198") (pin "2") (pinfunction "2_2") (pintype "passive"))
      (node (ref "R199") (pin "2") (pinfunction "2_2") (pintype "passive"))
      (node (ref "U42") (pin "3") (pinfunction "GND_3") (pintype "power_in"))
      (node (ref "U42") (pin "7") (pinfunction "PAD_7") (pintype "power_in"))
      (node (ref "U43") (pin "0") (pinfunction "PAD_0") (pintype "passive"))
      (node (ref "U43") (pin "4") (pinfunction "PGND_4") (pintype "passive"))
      (node (ref "U43") (pin "8") (pinfunction "GND_8") (pintype "passive"))
      (node (ref "VT1") (pin "2") (pinfunction "Sourse_2") (pintype "passive"))
    )
    (net (code "93") (name "Net-(HL10-Cathode)") (class "Default")
      (node (ref "HL10") (pin "2") (pinfunction "Cathode_2") (pintype "passive"))
      (node (ref "R174") (pin "2") (pinfunction "2_2") (pintype "passive"))
    )
    (net (code "94") (name "Net-(U42-CLKN)") (class "Default")
      (node (ref "C156") (pin "1") (pinfunction "1_1") (pintype "passive"))
      (node (ref "U42") (pin "5") (pinfunction "CLKN_5") (pintype "passive"))
    )
    (net (code "95") (name "Net-(U42-CLKP)") (class "Default")
      (node (ref "C157") (pin "1") (pinfunction "1_1") (pintype "passive"))
      (node (ref "U42") (pin "4") (pinfunction "CLKP_4") (pintype "passive"))
    )
    (net (code "96") (name "Net-(U42-OE)") (class "Default")
      (node (ref "R189") (pin "1") (pinfunction "1_1") (pintype "passive"))
      (node (ref "U42") (pin "1") (pinfunction "OE_1") (pintype "power_in"))
    )
    (net (code "97") (name "Net-(U42-VDD)") (class "Default")
      (node (ref "C168") (pin "2") (pinfunction "2_2") (pintype "passive"))
      (node (ref "L14") (pin "2") (pinfunction "2_2") (pintype "passive"))
      (node (ref "R189") (pin "2") (pinfunction "2_2") (pintype "passive"))
      (node (ref "U42") (pin "6") (pinfunction "VDD_6") (pintype "power_in"))
    )
    (net (code "98") (name "Net-(U43-PGOOD)") (class "Default")
      (node (ref "R196") (pin "2") (pinfunction "2_2") (pintype "passive"))
      (node (ref "U43") (pin "9") (pinfunction "PGOOD_9") (pintype "passive"))
    )
    (net (code "99") (name "Net-(U43-REFIN)") (class "Default")
      (node (ref "C162") (pin "1") (pinfunction "1_1") (pintype "passive"))
      (node (ref "R192") (pin "2") (pinfunction "2_2") (pintype "passive"))
      (node (ref "R195") (pin "2") (pinfunction "2_2") (pintype "passive"))
      (node (ref "U43") (pin "1") (pinfunction "REFIN_1") (pintype "passive"))
    )
    (net (code "100") (name "Net-(VT1-Drain)") (class "Default")
      (node (ref "R174") (pin "1") (pinfunction "1_1") (pintype "passive"))
      (node (ref "VT1") (pin "3") (pinfunction "Drain_3") (pintype "passive"))
    )
    (net (code "101") (name "VTTREF") (class "Default")
      (node (ref "C163") (pin "1") (pinfunction "1_1") (pintype "passive"))
      (node (ref "C164") (pin "1") (pinfunction "1_1") (pintype "passive"))
      (node (ref "U20") (pin "E3") (pinfunction "IO_L6N_T0_VREF_35_E3") (pintype "bidirectional"))
      (node (ref "U20") (pin "N3") (pinfunction "IO_L19N_T3_VREF_35_N3") (pintype "bidirectional"))
      (node (ref "U40") (pin "H1") (pinfunction "VREFDQ_H1") (pintype "power_in"))
      (node (ref "U40") (pin "M8") (pinfunction "VREFCA_M8") (pintype "power_in"))
      (node (ref "U41") (pin "H1") (pinfunction "VREFDQ_H1") (pintype "power_in"))
      (node (ref "U41") (pin "M8") (pinfunction "VREFCA_M8") (pintype "power_in"))
      (node (ref "U43") (pin "6") (pinfunction "REFOUT_6") (pintype "passive"))
    )
    (net (code "102") (name "unconnected-(U20E-IO_0_34-PadT3)") (class "Default")
      (node (ref "U20") (pin "T3") (pinfunction "IO_0_34_T3") (pintype "bidirectional"))
    )
    (net (code "103") (name "unconnected-(U20E-IO_25_34-PadU7)") (class "Default")
      (node (ref "U20") (pin "U7") (pinfunction "IO_25_34_U7") (pintype "bidirectional"))
    )
    (net (code "104") (name "unconnected-(U20E-IO_L6P_T0_34-PadU3)") (class "Default")
      (node (ref "U20") (pin "U3") (pinfunction "IO_L6P_T0_34_U3") (pintype "bidirectional"))
    )
    (net (code "105") (name "unconnected-(U20E-IO_L12P_T1_MRCC_34-PadV4)") (class "Default")
      (node (ref "U20") (pin "V4") (pinfunction "IO_L12P_T1_MRCC_34_V4") (pintype "bidirectional"))
    )
    (net (code "106") (name "unconnected-(U20E-IO_L14N_T2_SRCC_34-PadU5)") (class "Default")
      (node (ref "U20") (pin "U5") (pinfunction "IO_L14N_T2_SRCC_34_U5") (pintype "bidirectional"))
    )
    (net (code "107") (name "unconnected-(U20E-IO_L16N_T2_34-PadV5)") (class "Default")
      (node (ref "U20") (pin "V5") (pinfunction "IO_L16N_T2_34_V5") (pintype "bidirectional"))
    )
    (net (code "108") (name "unconnected-(U20E-IO_L17N_T2_34-PadT6)") (class "Default")
      (node (ref "U20") (pin "T6") (pinfunction "IO_L17N_T2_34_T6") (pintype "bidirectional"))
    )
    (net (code "109") (name "unconnected-(U20E-IO_L21P_T3_DQS_34-PadV9)") (class "Default")
      (node (ref "U20") (pin "V9") (pinfunction "IO_L21P_T3_DQS_34_V9") (pintype "bidirectional"))
    )
    (net (code "110") (name "unconnected-(U20F-IO_0_35-PadF4)") (class "Default")
      (node (ref "U20") (pin "F4") (pinfunction "IO_0_35_F4") (pintype "bidirectional"))
    )
    (net (code "111") (name "unconnected-(U20F-IO_25_35-PadL6)") (class "Default")
      (node (ref "U20") (pin "L6") (pinfunction "IO_25_35_L6") (pintype "bidirectional"))
    )
    (net (code "112") (name "unconnected-(U20F-IO_L12N_T1_MRCC_35-PadG4)") (class "Default")
      (node (ref "U20") (pin "G4") (pinfunction "IO_L12N_T1_MRCC_35_G4") (pintype "bidirectional"))
    )
    (net (code "113") (name "unconnected-(U20F-IO_L17N_T2_35-PadJ6)") (class "Default")
      (node (ref "U20") (pin "J6") (pinfunction "IO_L17N_T2_35_J6") (pintype "bidirectional"))
    )
    (net (code "114") (name "unconnected-(U42-NC-Pad2)") (class "Default")
      (node (ref "U42") (pin "2") (pinfunction "NC_2") (pintype "passive"))
    )
    (net (code "115") (name "unconnected-(U43-Pad173)") (class "Default")
      (node (ref "U43") (pin "173") (pintype "passive"))
    )
    (net (code "116") (name "unconnected-(U43-Pad174)") (class "Default")
      (node (ref "U43") (pin "174") (pintype "passive"))
    )
  )
)
